# zik-pcb-gpu-f407.net
KiCad netlist of a schematic drawn in EAGLE
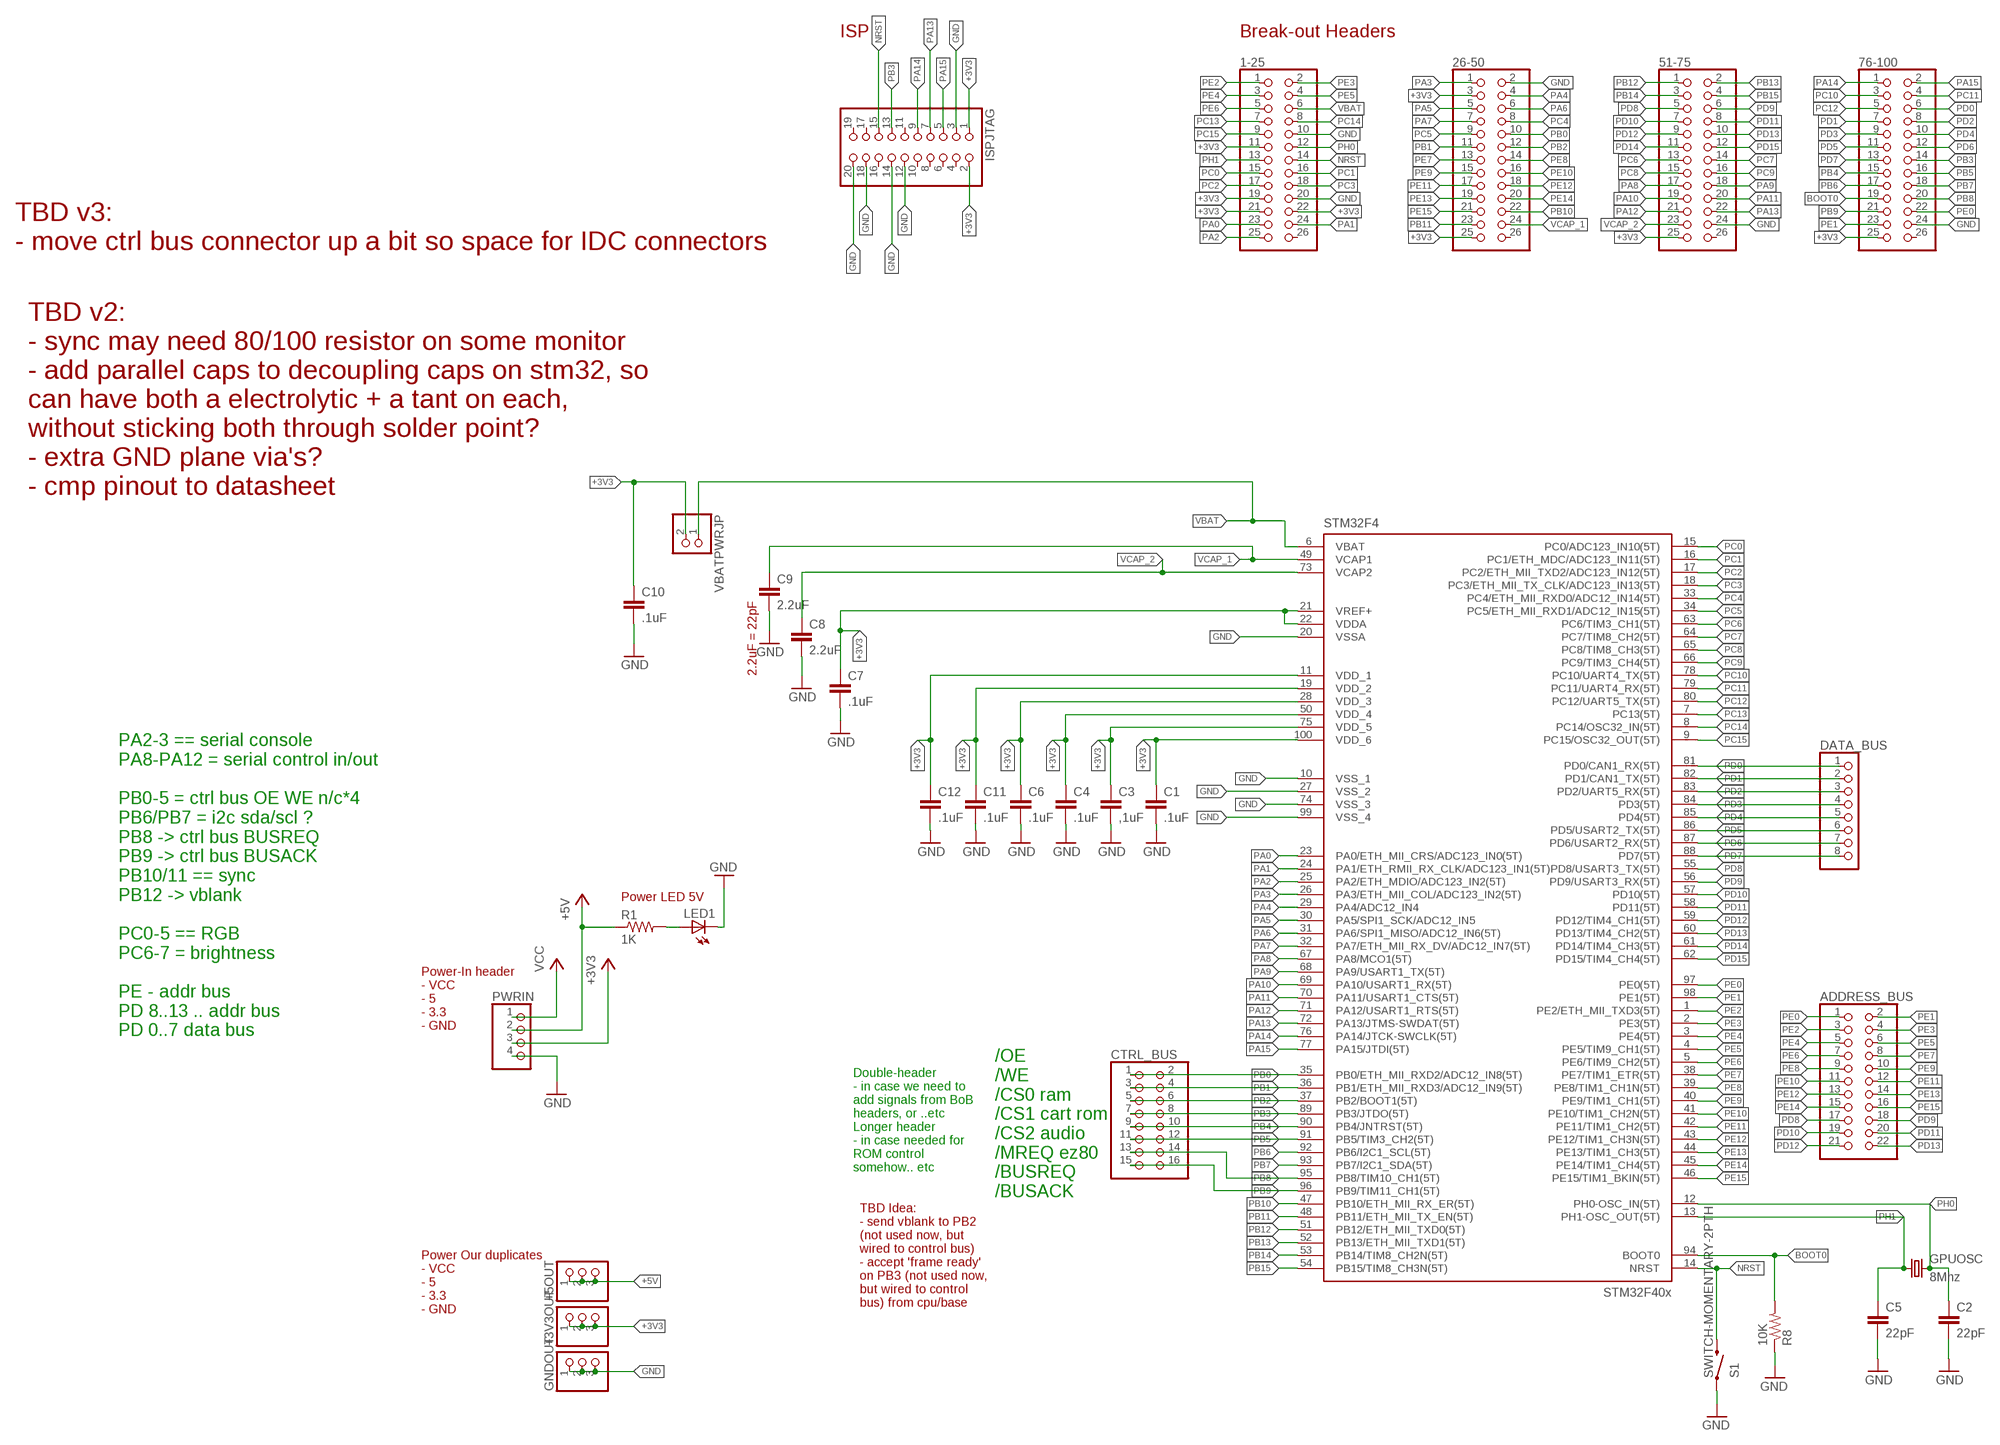
[diagram p0: schematic, sheet 1, part 1 of 2]
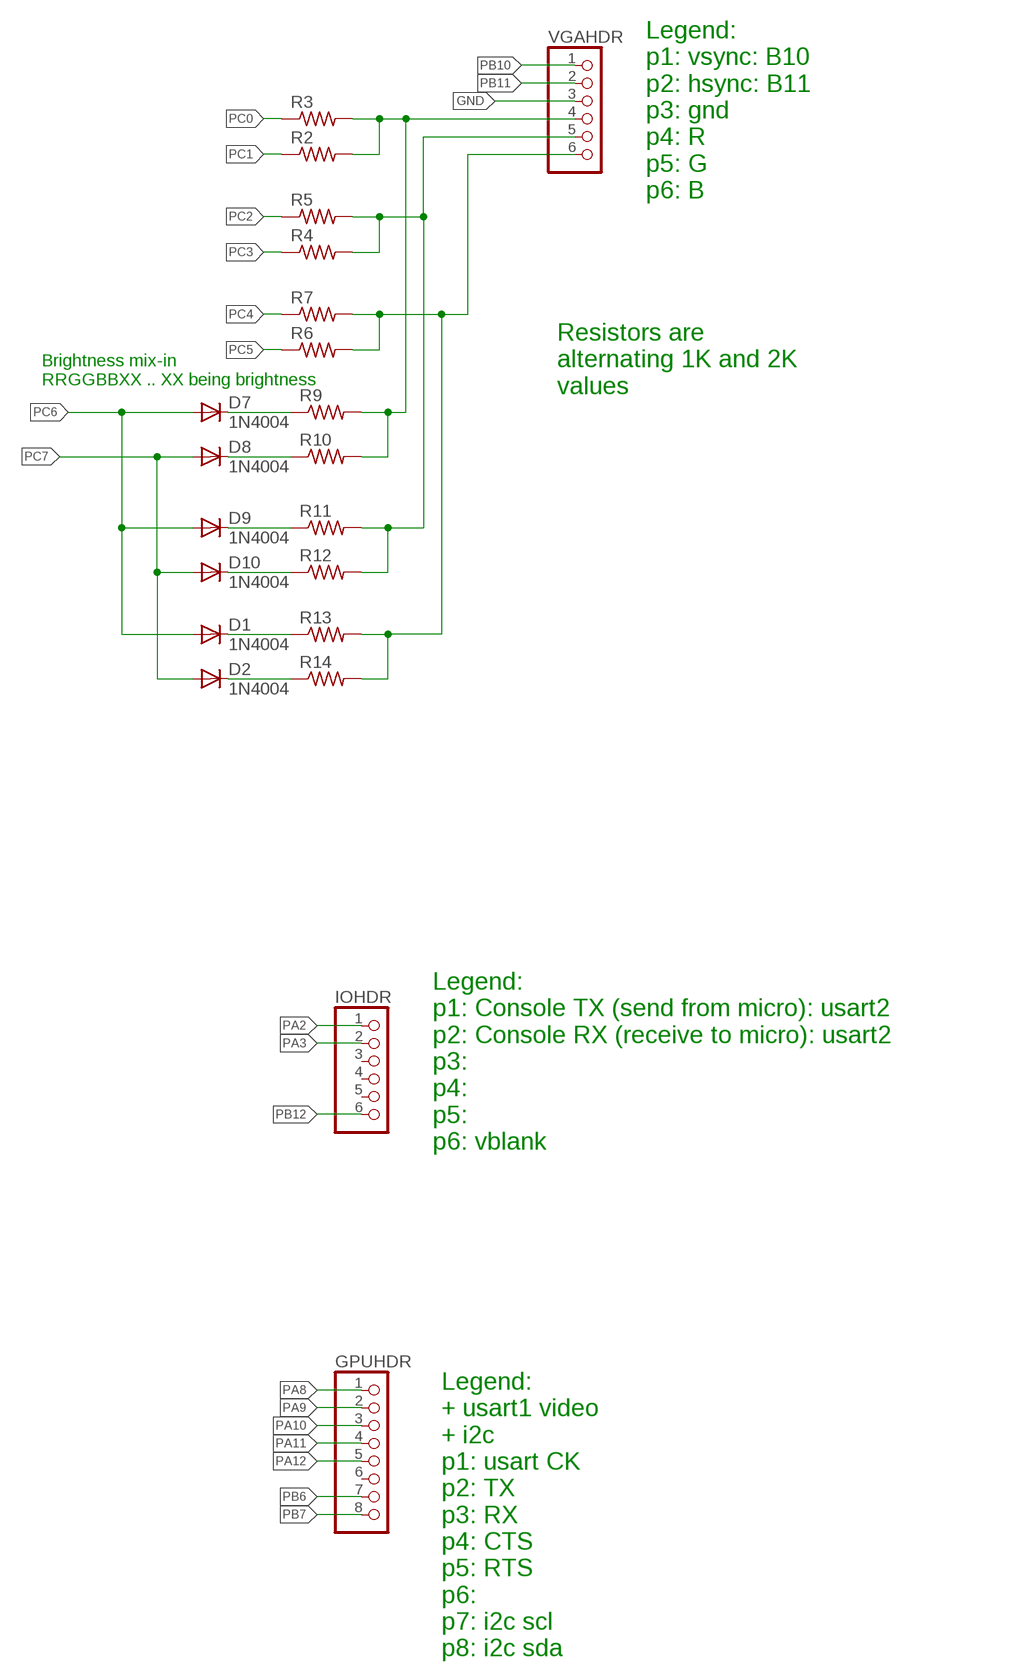
[diagram p1: schematic, sheet 1, part 2 of 2]

(export (version "E")
  (design (tool "Eeschema 10.0.6"))
  (components
    (comp (ref "+3V3OUT")
      (value "PINHD-1X3")
      (footprint "eagle-import:1X03")
      (libsource (lib "eagle-import") (part "PINHD-1X3"))
    )
    (comp (ref "+5OUT")
      (value "PINHD-1X3")
      (footprint "eagle-import:1X03")
      (libsource (lib "eagle-import") (part "PINHD-1X3"))
    )
    (comp (ref "1-25")
      (value "PINHD-2X13")
      (footprint "eagle-import:2X13")
      (libsource (lib "eagle-import") (part "PINHD-2X13"))
    )
    (comp (ref "26-50")
      (value "PINHD-2X13")
      (footprint "eagle-import:2X13")
      (libsource (lib "eagle-import") (part "PINHD-2X13"))
    )
    (comp (ref "51-75")
      (value "PINHD-2X13")
      (footprint "eagle-import:2X13")
      (libsource (lib "eagle-import") (part "PINHD-2X13"))
    )
    (comp (ref "76-100")
      (value "PINHD-2X13")
      (footprint "eagle-import:2X13")
      (libsource (lib "eagle-import") (part "PINHD-2X13"))
    )
    (comp (ref "ADDRESS_BUS")
      (value "PINHD-2X11")
      (footprint "eagle-import:2X11")
      (libsource (lib "eagle-import") (part "PINHD-2X11"))
    )
    (comp (ref "C1")
      (value ".1uF")
      (footprint "eagle-import:C025-025X050")
      (libsource (lib "eagle-import") (part "C-EU025-025X050"))
    )
    (comp (ref "C2")
      (value "22pF")
      (footprint "eagle-import:C025-025X050")
      (libsource (lib "eagle-import") (part "C-EU025-025X050"))
    )
    (comp (ref "C3")
      (value ",1uF")
      (footprint "eagle-import:C025-025X050")
      (libsource (lib "eagle-import") (part "C-EU025-025X050"))
    )
    (comp (ref "C4")
      (value ".1uF")
      (footprint "eagle-import:C025-025X050")
      (libsource (lib "eagle-import") (part "C-EU025-025X050"))
    )
    (comp (ref "C5")
      (value "22pF")
      (footprint "eagle-import:C025-025X050")
      (libsource (lib "eagle-import") (part "C-EU025-025X050"))
    )
    (comp (ref "C6")
      (value ".1uF")
      (footprint "eagle-import:C025-025X050")
      (libsource (lib "eagle-import") (part "C-EU025-025X050"))
    )
    (comp (ref "C7")
      (value ".1uF")
      (footprint "eagle-import:C025-025X050")
      (libsource (lib "eagle-import") (part "C-EU025-025X050"))
    )
    (comp (ref "C8")
      (value "2.2uF")
      (footprint "eagle-import:C025-025X050")
      (libsource (lib "eagle-import") (part "C-EU025-025X050"))
    )
    (comp (ref "C9")
      (value "2.2uF")
      (footprint "eagle-import:C025-025X050")
      (libsource (lib "eagle-import") (part "C-EU025-025X050"))
    )
    (comp (ref "C10")
      (value ".1uF")
      (footprint "eagle-import:C025-025X050")
      (libsource (lib "eagle-import") (part "C-EU025-025X050"))
    )
    (comp (ref "C11")
      (value ".1uF")
      (footprint "eagle-import:C025-025X050")
      (libsource (lib "eagle-import") (part "C-EU025-025X050"))
    )
    (comp (ref "C12")
      (value ".1uF")
      (footprint "eagle-import:C025-025X050")
      (libsource (lib "eagle-import") (part "C-EU025-025X050"))
    )
    (comp (ref "CTRL_BUS")
      (value "PINHD-2X8")
      (footprint "eagle-import:2X08")
      (libsource (lib "eagle-import") (part "PINHD-2X8"))
    )
    (comp (ref "D1")
      (value "1N4004")
      (footprint "eagle-import:DO41-10")
      (libsource (lib "eagle-import") (part "1N4004"))
    )
    (comp (ref "D2")
      (value "1N4004")
      (footprint "eagle-import:DO41-10")
      (libsource (lib "eagle-import") (part "1N4004"))
    )
    (comp (ref "D7")
      (value "1N4004")
      (footprint "eagle-import:DO41-10")
      (libsource (lib "eagle-import") (part "1N4004"))
    )
    (comp (ref "D8")
      (value "1N4004")
      (footprint "eagle-import:DO41-10")
      (libsource (lib "eagle-import") (part "1N4004"))
    )
    (comp (ref "D9")
      (value "1N4004")
      (footprint "eagle-import:DO41-10")
      (libsource (lib "eagle-import") (part "1N4004"))
    )
    (comp (ref "D10")
      (value "1N4004")
      (footprint "eagle-import:DO41-10")
      (libsource (lib "eagle-import") (part "1N4004"))
    )
    (comp (ref "DATA_BUS")
      (value "PINHD-1X8")
      (footprint "eagle-import:1X08")
      (libsource (lib "eagle-import") (part "PINHD-1X8"))
    )
    (comp (ref "GNDOUT")
      (value "PINHD-1X3")
      (footprint "eagle-import:1X03")
      (libsource (lib "eagle-import") (part "PINHD-1X3"))
    )
    (comp (ref "GPUHDR")
      (value "PINHD-1X8")
      (footprint "eagle-import:1X08")
      (libsource (lib "eagle-import") (part "PINHD-1X8"))
    )
    (comp (ref "GPUOSC")
      (value "8Mhz")
      (footprint "eagle-import:HC49US")
      (libsource (lib "eagle-import") (part "CRYSTALHC49US"))
    )
    (comp (ref "IOHDR")
      (value "PINHD-1X6")
      (footprint "eagle-import:1X06")
      (libsource (lib "eagle-import") (part "PINHD-1X6"))
    )
    (comp (ref "ISPJTAG")
      (value "PINHD-2X10")
      (footprint "eagle-import:2X10")
      (libsource (lib "eagle-import") (part "PINHD-2X10"))
    )
    (comp (ref "LED1")
      (value "LED5MM")
      (footprint "eagle-import:LED5MM")
      (libsource (lib "eagle-import") (part "LED5MM"))
    )
    (comp (ref "PWRIN")
      (value "PINHD-1X4")
      (footprint "eagle-import:1X04")
      (libsource (lib "eagle-import") (part "PINHD-1X4"))
    )
    (comp (ref "R1")
      (value "1K")
      (footprint "eagle-import:0207_10")
      (libsource (lib "eagle-import") (part "R-US_0207/10"))
    )
    (comp (ref "R2")
      (value "R-US_0207/10")
      (footprint "eagle-import:0207_10")
      (libsource (lib "eagle-import") (part "R-US_0207/10"))
    )
    (comp (ref "R3")
      (value "R-US_0207/10")
      (footprint "eagle-import:0207_10")
      (libsource (lib "eagle-import") (part "R-US_0207/10"))
    )
    (comp (ref "R4")
      (value "R-US_0207/10")
      (footprint "eagle-import:0207_10")
      (libsource (lib "eagle-import") (part "R-US_0207/10"))
    )
    (comp (ref "R5")
      (value "R-US_0207/10")
      (footprint "eagle-import:0207_10")
      (libsource (lib "eagle-import") (part "R-US_0207/10"))
    )
    (comp (ref "R6")
      (value "R-US_0207/10")
      (footprint "eagle-import:0207_10")
      (libsource (lib "eagle-import") (part "R-US_0207/10"))
    )
    (comp (ref "R7")
      (value "R-US_0207/10")
      (footprint "eagle-import:0207_10")
      (libsource (lib "eagle-import") (part "R-US_0207/10"))
    )
    (comp (ref "R8")
      (value "10K")
      (footprint "eagle-import:0207_10")
      (libsource (lib "eagle-import") (part "R-US_0207/10"))
    )
    (comp (ref "R9")
      (value "R-US_0207/10")
      (footprint "eagle-import:0207_10")
      (libsource (lib "eagle-import") (part "R-US_0207/10"))
    )
    (comp (ref "R10")
      (value "R-US_0207/10")
      (footprint "eagle-import:0207_10")
      (libsource (lib "eagle-import") (part "R-US_0207/10"))
    )
    (comp (ref "R11")
      (value "R-US_0207/10")
      (footprint "eagle-import:0207_10")
      (libsource (lib "eagle-import") (part "R-US_0207/10"))
    )
    (comp (ref "R12")
      (value "R-US_0207/10")
      (footprint "eagle-import:0207_10")
      (libsource (lib "eagle-import") (part "R-US_0207/10"))
    )
    (comp (ref "R13")
      (value "R-US_0207/10")
      (footprint "eagle-import:0207_10")
      (libsource (lib "eagle-import") (part "R-US_0207/10"))
    )
    (comp (ref "R14")
      (value "R-US_0207/10")
      (footprint "eagle-import:0207_10")
      (libsource (lib "eagle-import") (part "R-US_0207/10"))
    )
    (comp (ref "S1")
      (value "SWITCH-MOMENTARY-2PTH")
      (footprint "eagle-import:TACTILE-PTH")
      (libsource (lib "eagle-import") (part "SWITCH-MOMENTARY-2PTH"))
    )
    (comp (ref "STM32F4")
      (value "STM32F407V")
      (footprint "eagle-import:TQFP100")
      (libsource (lib "eagle-import") (part "STM32F407V"))
    )
    (comp (ref "VBATPWRJP")
      (value "PINHD-1X2")
      (footprint "eagle-import:1X02")
      (libsource (lib "eagle-import") (part "PINHD-1X2"))
    )
    (comp (ref "VGAHDR")
      (value "PINHD-1X6")
      (footprint "eagle-import:1X06")
      (libsource (lib "eagle-import") (part "PINHD-1X6"))
    )
  )
  (nets
    (net (code "1") (name "+3V3") (class "Default")
      (node (ref "+3V3OUT") (pin "1") (pinfunction "1_1") (pintype "passive"))
      (node (ref "+3V3OUT") (pin "2") (pinfunction "2_2") (pintype "passive"))
      (node (ref "+3V3OUT") (pin "3") (pinfunction "3_3") (pintype "passive"))
      (node (ref "1-25") (pin "11") (pinfunction "11_11") (pintype "passive"))
      (node (ref "1-25") (pin "19") (pinfunction "19_19") (pintype "passive"))
      (node (ref "1-25") (pin "21") (pinfunction "21_21") (pintype "passive"))
      (node (ref "1-25") (pin "22") (pinfunction "22_22") (pintype "passive"))
      (node (ref "26-50") (pin "25") (pinfunction "25_25") (pintype "passive"))
      (node (ref "26-50") (pin "3") (pinfunction "3_3") (pintype "passive"))
      (node (ref "51-75") (pin "25") (pinfunction "25_25") (pintype "passive"))
      (node (ref "76-100") (pin "25") (pinfunction "25_25") (pintype "passive"))
      (node (ref "C1") (pin "1") (pinfunction "1_1") (pintype "passive"))
      (node (ref "C10") (pin "1") (pinfunction "1_1") (pintype "passive"))
      (node (ref "C11") (pin "1") (pinfunction "1_1") (pintype "passive"))
      (node (ref "C12") (pin "1") (pinfunction "1_1") (pintype "passive"))
      (node (ref "C3") (pin "1") (pinfunction "1_1") (pintype "passive"))
      (node (ref "C4") (pin "1") (pinfunction "1_1") (pintype "passive"))
      (node (ref "C6") (pin "1") (pinfunction "1_1") (pintype "passive"))
      (node (ref "C7") (pin "1") (pinfunction "1_1") (pintype "passive"))
      (node (ref "ISPJTAG") (pin "1") (pinfunction "1_1") (pintype "passive"))
      (node (ref "ISPJTAG") (pin "2") (pinfunction "2_2") (pintype "passive"))
      (node (ref "PWRIN") (pin "3") (pinfunction "3_3") (pintype "passive"))
      (node (ref "STM32F4") (pin "100") (pinfunction "VDD_6_100") (pintype "bidirectional"))
      (node (ref "STM32F4") (pin "11") (pinfunction "VDD_1_11") (pintype "bidirectional"))
      (node (ref "STM32F4") (pin "19") (pinfunction "VDD_2_19") (pintype "bidirectional"))
      (node (ref "STM32F4") (pin "21") (pinfunction "VREF+_21") (pintype "bidirectional"))
      (node (ref "STM32F4") (pin "22") (pinfunction "VDDA_22") (pintype "bidirectional"))
      (node (ref "STM32F4") (pin "28") (pinfunction "VDD_3_28") (pintype "bidirectional"))
      (node (ref "STM32F4") (pin "50") (pinfunction "VDD_4_50") (pintype "bidirectional"))
      (node (ref "STM32F4") (pin "75") (pinfunction "VDD_5_75") (pintype "bidirectional"))
      (node (ref "VBATPWRJP") (pin "2") (pinfunction "2_2") (pintype "passive"))
    )
    (net (code "2") (name "+5V") (class "Default")
      (node (ref "+5OUT") (pin "1") (pinfunction "1_1") (pintype "passive"))
      (node (ref "+5OUT") (pin "2") (pinfunction "2_2") (pintype "passive"))
      (node (ref "+5OUT") (pin "3") (pinfunction "3_3") (pintype "passive"))
      (node (ref "PWRIN") (pin "2") (pinfunction "2_2") (pintype "passive"))
      (node (ref "R1") (pin "1") (pinfunction "1_1") (pintype "passive"))
    )
    (net (code "3") (name "BOOT0") (class "Default")
      (node (ref "76-100") (pin "19") (pinfunction "19_19") (pintype "passive"))
      (node (ref "R8") (pin "2") (pinfunction "2_2") (pintype "passive"))
      (node (ref "STM32F4") (pin "94") (pinfunction "BOOT0_94") (pintype "bidirectional"))
    )
    (net (code "4") (name "GND") (class "Default")
      (node (ref "1-25") (pin "10") (pinfunction "10_10") (pintype "passive"))
      (node (ref "1-25") (pin "20") (pinfunction "20_20") (pintype "passive"))
      (node (ref "26-50") (pin "2") (pinfunction "2_2") (pintype "passive"))
      (node (ref "51-75") (pin "24") (pinfunction "24_24") (pintype "passive"))
      (node (ref "76-100") (pin "24") (pinfunction "24_24") (pintype "passive"))
      (node (ref "C1") (pin "2") (pinfunction "2_2") (pintype "passive"))
      (node (ref "C10") (pin "2") (pinfunction "2_2") (pintype "passive"))
      (node (ref "C11") (pin "2") (pinfunction "2_2") (pintype "passive"))
      (node (ref "C12") (pin "2") (pinfunction "2_2") (pintype "passive"))
      (node (ref "C2") (pin "2") (pinfunction "2_2") (pintype "passive"))
      (node (ref "C3") (pin "2") (pinfunction "2_2") (pintype "passive"))
      (node (ref "C4") (pin "2") (pinfunction "2_2") (pintype "passive"))
      (node (ref "C5") (pin "2") (pinfunction "2_2") (pintype "passive"))
      (node (ref "C6") (pin "2") (pinfunction "2_2") (pintype "passive"))
      (node (ref "C7") (pin "2") (pinfunction "2_2") (pintype "passive"))
      (node (ref "C8") (pin "2") (pinfunction "2_2") (pintype "passive"))
      (node (ref "C9") (pin "2") (pinfunction "2_2") (pintype "passive"))
      (node (ref "GNDOUT") (pin "1") (pinfunction "1_1") (pintype "passive"))
      (node (ref "GNDOUT") (pin "2") (pinfunction "2_2") (pintype "passive"))
      (node (ref "GNDOUT") (pin "3") (pinfunction "3_3") (pintype "passive"))
      (node (ref "ISPJTAG") (pin "12") (pinfunction "12_12") (pintype "passive"))
      (node (ref "ISPJTAG") (pin "14") (pinfunction "14_14") (pintype "passive"))
      (node (ref "ISPJTAG") (pin "18") (pinfunction "18_18") (pintype "passive"))
      (node (ref "ISPJTAG") (pin "20") (pinfunction "20_20") (pintype "passive"))
      (node (ref "ISPJTAG") (pin "3") (pinfunction "3_3") (pintype "passive"))
      (node (ref "LED1") (pin "K") (pinfunction "C_K") (pintype "passive"))
      (node (ref "PWRIN") (pin "4") (pinfunction "4_4") (pintype "passive"))
      (node (ref "R8") (pin "1") (pinfunction "1_1") (pintype "passive"))
      (node (ref "S1") (pin "1") (pinfunction "1_1") (pintype "passive"))
      (node (ref "STM32F4") (pin "10") (pinfunction "VSS_1_10") (pintype "bidirectional"))
      (node (ref "STM32F4") (pin "20") (pinfunction "VSSA_20") (pintype "bidirectional"))
      (node (ref "STM32F4") (pin "27") (pinfunction "VSS_2_27") (pintype "bidirectional"))
      (node (ref "STM32F4") (pin "74") (pinfunction "VSS_3_74") (pintype "bidirectional"))
      (node (ref "STM32F4") (pin "99") (pinfunction "VSS_4_99") (pintype "bidirectional"))
      (node (ref "VGAHDR") (pin "3") (pinfunction "3_3") (pintype "passive"))
    )
    (net (code "5") (name "NRST") (class "Default")
      (node (ref "1-25") (pin "14") (pinfunction "14_14") (pintype "passive"))
      (node (ref "ISPJTAG") (pin "15") (pinfunction "15_15") (pintype "passive"))
      (node (ref "S1") (pin "3") (pinfunction "2_3") (pintype "passive"))
      (node (ref "STM32F4") (pin "14") (pinfunction "NRST_14") (pintype "bidirectional"))
    )
    (net (code "6") (name "Net-(D1-PadC)") (class "Default")
      (node (ref "D1") (pin "C") (pinfunction "C_C") (pintype "passive"))
      (node (ref "R13") (pin "1") (pinfunction "1_1") (pintype "passive"))
    )
    (net (code "7") (name "Net-(D2-PadC)") (class "Default")
      (node (ref "D2") (pin "C") (pinfunction "C_C") (pintype "passive"))
      (node (ref "R14") (pin "1") (pinfunction "1_1") (pintype "passive"))
    )
    (net (code "8") (name "Net-(D7-PadC)") (class "Default")
      (node (ref "D7") (pin "C") (pinfunction "C_C") (pintype "passive"))
      (node (ref "R9") (pin "1") (pinfunction "1_1") (pintype "passive"))
    )
    (net (code "9") (name "Net-(D8-PadC)") (class "Default")
      (node (ref "D8") (pin "C") (pinfunction "C_C") (pintype "passive"))
      (node (ref "R10") (pin "1") (pinfunction "1_1") (pintype "passive"))
    )
    (net (code "10") (name "Net-(D9-PadC)") (class "Default")
      (node (ref "D9") (pin "C") (pinfunction "C_C") (pintype "passive"))
      (node (ref "R11") (pin "1") (pinfunction "1_1") (pintype "passive"))
    )
    (net (code "11") (name "Net-(D10-PadC)") (class "Default")
      (node (ref "D10") (pin "C") (pinfunction "C_C") (pintype "passive"))
      (node (ref "R12") (pin "1") (pinfunction "1_1") (pintype "passive"))
    )
    (net (code "12") (name "Net-(LED1-PadA)") (class "Default")
      (node (ref "LED1") (pin "A") (pinfunction "A_A") (pintype "passive"))
      (node (ref "R1") (pin "2") (pinfunction "2_2") (pintype "passive"))
    )
    (net (code "13") (name "Net-(R10-Pad2)") (class "Default")
      (node (ref "R10") (pin "2") (pinfunction "2_2") (pintype "passive"))
      (node (ref "R2") (pin "2") (pinfunction "2_2") (pintype "passive"))
      (node (ref "R3") (pin "2") (pinfunction "2_2") (pintype "passive"))
      (node (ref "R9") (pin "2") (pinfunction "2_2") (pintype "passive"))
      (node (ref "VGAHDR") (pin "4") (pinfunction "4_4") (pintype "passive"))
    )
    (net (code "14") (name "Net-(R11-Pad2)") (class "Default")
      (node (ref "R11") (pin "2") (pinfunction "2_2") (pintype "passive"))
      (node (ref "R12") (pin "2") (pinfunction "2_2") (pintype "passive"))
      (node (ref "R4") (pin "2") (pinfunction "2_2") (pintype "passive"))
      (node (ref "R5") (pin "2") (pinfunction "2_2") (pintype "passive"))
      (node (ref "VGAHDR") (pin "5") (pinfunction "5_5") (pintype "passive"))
    )
    (net (code "15") (name "Net-(R13-Pad2)") (class "Default")
      (node (ref "R13") (pin "2") (pinfunction "2_2") (pintype "passive"))
      (node (ref "R14") (pin "2") (pinfunction "2_2") (pintype "passive"))
      (node (ref "R6") (pin "2") (pinfunction "2_2") (pintype "passive"))
      (node (ref "R7") (pin "2") (pinfunction "2_2") (pintype "passive"))
      (node (ref "VGAHDR") (pin "6") (pinfunction "6_6") (pintype "passive"))
    )
    (net (code "16") (name "PA0") (class "Default")
      (node (ref "1-25") (pin "23") (pinfunction "23_23") (pintype "passive"))
      (node (ref "STM32F4") (pin "23") (pinfunction "PA0/ETH_MII_CRS/ADC123_IN0(5T)_23") (pintype "bidirectional"))
    )
    (net (code "17") (name "PA1") (class "Default")
      (node (ref "1-25") (pin "24") (pinfunction "24_24") (pintype "passive"))
      (node (ref "STM32F4") (pin "24") (pinfunction "PA1/ETH_RMII_RX_CLK/ADC123_IN1(5T)_24") (pintype "bidirectional"))
    )
    (net (code "18") (name "PA2") (class "Default")
      (node (ref "1-25") (pin "25") (pinfunction "25_25") (pintype "passive"))
      (node (ref "IOHDR") (pin "1") (pinfunction "1_1") (pintype "passive"))
      (node (ref "STM32F4") (pin "25") (pinfunction "PA2/ETH_MDIO/ADC123_IN2(5T)_25") (pintype "bidirectional"))
    )
    (net (code "19") (name "PA3") (class "Default")
      (node (ref "26-50") (pin "1") (pinfunction "1_1") (pintype "passive"))
      (node (ref "IOHDR") (pin "2") (pinfunction "2_2") (pintype "passive"))
      (node (ref "STM32F4") (pin "26") (pinfunction "PA3/ETH_MII_COL/ADC123_IN2(5T)_26") (pintype "bidirectional"))
    )
    (net (code "20") (name "PA4") (class "Default")
      (node (ref "26-50") (pin "4") (pinfunction "4_4") (pintype "passive"))
      (node (ref "STM32F4") (pin "29") (pinfunction "PA4/ADC12_IN4_29") (pintype "bidirectional"))
    )
    (net (code "21") (name "PA5") (class "Default")
      (node (ref "26-50") (pin "5") (pinfunction "5_5") (pintype "passive"))
      (node (ref "STM32F4") (pin "30") (pinfunction "PA5/SPI1_SCK/ADC12_IN5_30") (pintype "bidirectional"))
    )
    (net (code "22") (name "PA6") (class "Default")
      (node (ref "26-50") (pin "6") (pinfunction "6_6") (pintype "passive"))
      (node (ref "STM32F4") (pin "31") (pinfunction "PA6/SPI1_MISO/ADC12_IN6(5T)_31") (pintype "bidirectional"))
    )
    (net (code "23") (name "PA7") (class "Default")
      (node (ref "26-50") (pin "7") (pinfunction "7_7") (pintype "passive"))
      (node (ref "STM32F4") (pin "32") (pinfunction "PA7/ETH_MII_RX_DV/ADC12_IN7(5T)_32") (pintype "bidirectional"))
    )
    (net (code "24") (name "PA8") (class "Default")
      (node (ref "51-75") (pin "17") (pinfunction "17_17") (pintype "passive"))
      (node (ref "GPUHDR") (pin "1") (pinfunction "1_1") (pintype "passive"))
      (node (ref "STM32F4") (pin "67") (pinfunction "PA8/MCO1(5T)_67") (pintype "bidirectional"))
    )
    (net (code "25") (name "PA9") (class "Default")
      (node (ref "51-75") (pin "18") (pinfunction "18_18") (pintype "passive"))
      (node (ref "GPUHDR") (pin "2") (pinfunction "2_2") (pintype "passive"))
      (node (ref "STM32F4") (pin "68") (pinfunction "PA9/USART1_TX(5T)_68") (pintype "bidirectional"))
    )
    (net (code "26") (name "PA10") (class "Default")
      (node (ref "51-75") (pin "19") (pinfunction "19_19") (pintype "passive"))
      (node (ref "GPUHDR") (pin "3") (pinfunction "3_3") (pintype "passive"))
      (node (ref "STM32F4") (pin "69") (pinfunction "PA10/USART1_RX(5T)_69") (pintype "bidirectional"))
    )
    (net (code "27") (name "PA11") (class "Default")
      (node (ref "51-75") (pin "20") (pinfunction "20_20") (pintype "passive"))
      (node (ref "GPUHDR") (pin "4") (pinfunction "4_4") (pintype "passive"))
      (node (ref "STM32F4") (pin "70") (pinfunction "PA11/USART1_CTS(5T)_70") (pintype "bidirectional"))
    )
    (net (code "28") (name "PA12") (class "Default")
      (node (ref "51-75") (pin "21") (pinfunction "21_21") (pintype "passive"))
      (node (ref "GPUHDR") (pin "5") (pinfunction "5_5") (pintype "passive"))
      (node (ref "STM32F4") (pin "71") (pinfunction "PA12/USART1_RTS(5T)_71") (pintype "bidirectional"))
    )
    (net (code "29") (name "PA13") (class "Default")
      (node (ref "51-75") (pin "22") (pinfunction "22_22") (pintype "passive"))
      (node (ref "ISPJTAG") (pin "7") (pinfunction "7_7") (pintype "passive"))
      (node (ref "STM32F4") (pin "72") (pinfunction "PA13/JTMS-SWDAT(5T)_72") (pintype "bidirectional"))
    )
    (net (code "30") (name "PA14") (class "Default")
      (node (ref "76-100") (pin "1") (pinfunction "1_1") (pintype "passive"))
      (node (ref "ISPJTAG") (pin "9") (pinfunction "9_9") (pintype "passive"))
      (node (ref "STM32F4") (pin "76") (pinfunction "PA14/JTCK-SWCLK(5T)_76") (pintype "bidirectional"))
    )
    (net (code "31") (name "PA15") (class "Default")
      (node (ref "76-100") (pin "2") (pinfunction "2_2") (pintype "passive"))
      (node (ref "ISPJTAG") (pin "5") (pinfunction "5_5") (pintype "passive"))
      (node (ref "STM32F4") (pin "77") (pinfunction "PA15/JTDI(5T)_77") (pintype "bidirectional"))
    )
    (net (code "32") (name "PB0") (class "Default")
      (node (ref "26-50") (pin "10") (pinfunction "10_10") (pintype "passive"))
      (node (ref "CTRL_BUS") (pin "1") (pinfunction "1_1") (pintype "passive"))
      (node (ref "CTRL_BUS") (pin "2") (pinfunction "2_2") (pintype "passive"))
      (node (ref "STM32F4") (pin "35") (pinfunction "PB0/ETH_MII_RXD2/ADC12_IN8(5T)_35") (pintype "bidirectional"))
    )
    (net (code "33") (name "PB1") (class "Default")
      (node (ref "26-50") (pin "11") (pinfunction "11_11") (pintype "passive"))
      (node (ref "CTRL_BUS") (pin "3") (pinfunction "3_3") (pintype "passive"))
      (node (ref "CTRL_BUS") (pin "4") (pinfunction "4_4") (pintype "passive"))
      (node (ref "STM32F4") (pin "36") (pinfunction "PB1/ETH_MII_RXD3/ADC12_IN9(5T)_36") (pintype "bidirectional"))
    )
    (net (code "34") (name "PB2") (class "Default")
      (node (ref "26-50") (pin "12") (pinfunction "12_12") (pintype "passive"))
      (node (ref "CTRL_BUS") (pin "5") (pinfunction "5_5") (pintype "passive"))
      (node (ref "CTRL_BUS") (pin "6") (pinfunction "6_6") (pintype "passive"))
      (node (ref "STM32F4") (pin "37") (pinfunction "PB2/BOOT1(5T)_37") (pintype "bidirectional"))
    )
    (net (code "35") (name "PB3") (class "Default")
      (node (ref "76-100") (pin "14") (pinfunction "14_14") (pintype "passive"))
      (node (ref "CTRL_BUS") (pin "7") (pinfunction "7_7") (pintype "passive"))
      (node (ref "CTRL_BUS") (pin "8") (pinfunction "8_8") (pintype "passive"))
      (node (ref "ISPJTAG") (pin "13") (pinfunction "13_13") (pintype "passive"))
      (node (ref "STM32F4") (pin "89") (pinfunction "PB3/JTDO(5T)_89") (pintype "bidirectional"))
    )
    (net (code "36") (name "PB4") (class "Default")
      (node (ref "76-100") (pin "15") (pinfunction "15_15") (pintype "passive"))
      (node (ref "CTRL_BUS") (pin "10") (pinfunction "10_10") (pintype "passive"))
      (node (ref "CTRL_BUS") (pin "9") (pinfunction "9_9") (pintype "passive"))
      (node (ref "STM32F4") (pin "90") (pinfunction "PB4/JNTRST(5T)_90") (pintype "bidirectional"))
    )
    (net (code "37") (name "PB5") (class "Default")
      (node (ref "76-100") (pin "16") (pinfunction "16_16") (pintype "passive"))
      (node (ref "CTRL_BUS") (pin "11") (pinfunction "11_11") (pintype "passive"))
      (node (ref "CTRL_BUS") (pin "12") (pinfunction "12_12") (pintype "passive"))
      (node (ref "STM32F4") (pin "91") (pinfunction "PB5/TIM3_CH2(5T)_91") (pintype "bidirectional"))
    )
    (net (code "38") (name "PB6") (class "Default")
      (node (ref "76-100") (pin "17") (pinfunction "17_17") (pintype "passive"))
      (node (ref "GPUHDR") (pin "7") (pinfunction "7_7") (pintype "passive"))
      (node (ref "STM32F4") (pin "92") (pinfunction "PB6/I2C1_SCL(5T)_92") (pintype "bidirectional"))
    )
    (net (code "39") (name "PB7") (class "Default")
      (node (ref "76-100") (pin "18") (pinfunction "18_18") (pintype "passive"))
      (node (ref "GPUHDR") (pin "8") (pinfunction "8_8") (pintype "passive"))
      (node (ref "STM32F4") (pin "93") (pinfunction "PB7/I2C1_SDA(5T)_93") (pintype "bidirectional"))
    )
    (net (code "40") (name "PB8") (class "Default")
      (node (ref "76-100") (pin "20") (pinfunction "20_20") (pintype "passive"))
      (node (ref "CTRL_BUS") (pin "13") (pinfunction "13_13") (pintype "passive"))
      (node (ref "CTRL_BUS") (pin "14") (pinfunction "14_14") (pintype "passive"))
      (node (ref "STM32F4") (pin "95") (pinfunction "PB8/TIM10_CH1(5T)_95") (pintype "bidirectional"))
    )
    (net (code "41") (name "PB9") (class "Default")
      (node (ref "76-100") (pin "21") (pinfunction "21_21") (pintype "passive"))
      (node (ref "CTRL_BUS") (pin "15") (pinfunction "15_15") (pintype "passive"))
      (node (ref "CTRL_BUS") (pin "16") (pinfunction "16_16") (pintype "passive"))
      (node (ref "STM32F4") (pin "96") (pinfunction "PB9/TIM11_CH1(5T)_96") (pintype "bidirectional"))
    )
    (net (code "42") (name "PB10") (class "Default")
      (node (ref "26-50") (pin "22") (pinfunction "22_22") (pintype "passive"))
      (node (ref "STM32F4") (pin "47") (pinfunction "PB10/ETH_MII_RX_ER(5T)_47") (pintype "bidirectional"))
      (node (ref "VGAHDR") (pin "1") (pinfunction "1_1") (pintype "passive"))
    )
    (net (code "43") (name "PB11") (class "Default")
      (node (ref "26-50") (pin "23") (pinfunction "23_23") (pintype "passive"))
      (node (ref "STM32F4") (pin "48") (pinfunction "PB11/ETH_MII_TX_EN(5T)_48") (pintype "bidirectional"))
      (node (ref "VGAHDR") (pin "2") (pinfunction "2_2") (pintype "passive"))
    )
    (net (code "44") (name "PB12") (class "Default")
      (node (ref "51-75") (pin "1") (pinfunction "1_1") (pintype "passive"))
      (node (ref "IOHDR") (pin "6") (pinfunction "6_6") (pintype "passive"))
      (node (ref "STM32F4") (pin "51") (pinfunction "PB12/ETH_MII_TXD0(5T)_51") (pintype "bidirectional"))
    )
    (net (code "45") (name "PB13") (class "Default")
      (node (ref "51-75") (pin "2") (pinfunction "2_2") (pintype "passive"))
      (node (ref "STM32F4") (pin "52") (pinfunction "PB13/ETH_MII_TXD1(5T)_52") (pintype "bidirectional"))
    )
    (net (code "46") (name "PB14") (class "Default")
      (node (ref "51-75") (pin "3") (pinfunction "3_3") (pintype "passive"))
      (node (ref "STM32F4") (pin "53") (pinfunction "PB14/TIM8_CH2N(5T)_53") (pintype "bidirectional"))
    )
    (net (code "47") (name "PB15") (class "Default")
      (node (ref "51-75") (pin "4") (pinfunction "4_4") (pintype "passive"))
      (node (ref "STM32F4") (pin "54") (pinfunction "PB15/TIM8_CH3N(5T)_54") (pintype "bidirectional"))
    )
    (net (code "48") (name "PC0") (class "Default")
      (node (ref "1-25") (pin "15") (pinfunction "15_15") (pintype "passive"))
      (node (ref "R3") (pin "1") (pinfunction "1_1") (pintype "passive"))
      (node (ref "STM32F4") (pin "15") (pinfunction "PC0/ADC123_IN10(5T)_15") (pintype "bidirectional"))
    )
    (net (code "49") (name "PC1") (class "Default")
      (node (ref "1-25") (pin "16") (pinfunction "16_16") (pintype "passive"))
      (node (ref "R2") (pin "1") (pinfunction "1_1") (pintype "passive"))
      (node (ref "STM32F4") (pin "16") (pinfunction "PC1/ETH_MDC/ADC123_IN11(5T)_16") (pintype "bidirectional"))
    )
    (net (code "50") (name "PC2") (class "Default")
      (node (ref "1-25") (pin "17") (pinfunction "17_17") (pintype "passive"))
      (node (ref "R5") (pin "1") (pinfunction "1_1") (pintype "passive"))
      (node (ref "STM32F4") (pin "17") (pinfunction "PC2/ETH_MII_TXD2/ADC123_IN12(5T)_17") (pintype "bidirectional"))
    )
    (net (code "51") (name "PC3") (class "Default")
      (node (ref "1-25") (pin "18") (pinfunction "18_18") (pintype "passive"))
      (node (ref "R4") (pin "1") (pinfunction "1_1") (pintype "passive"))
      (node (ref "STM32F4") (pin "18") (pinfunction "PC3/ETH_MII_TX_CLK/ADC123_IN13(5T)_18") (pintype "bidirectional"))
    )
    (net (code "52") (name "PC4") (class "Default")
      (node (ref "26-50") (pin "8") (pinfunction "8_8") (pintype "passive"))
      (node (ref "R7") (pin "1") (pinfunction "1_1") (pintype "passive"))
      (node (ref "STM32F4") (pin "33") (pinfunction "PC4/ETH_MII_RXD0/ADC12_IN14(5T)_33") (pintype "bidirectional"))
    )
    (net (code "53") (name "PC5") (class "Default")
      (node (ref "26-50") (pin "9") (pinfunction "9_9") (pintype "passive"))
      (node (ref "R6") (pin "1") (pinfunction "1_1") (pintype "passive"))
      (node (ref "STM32F4") (pin "34") (pinfunction "PC5/ETH_MII_RXD1/ADC12_IN15(5T)_34") (pintype "bidirectional"))
    )
    (net (code "54") (name "PC6") (class "Default")
      (node (ref "51-75") (pin "13") (pinfunction "13_13") (pintype "passive"))
      (node (ref "D1") (pin "A") (pinfunction "A_A") (pintype "passive"))
      (node (ref "D7") (pin "A") (pinfunction "A_A") (pintype "passive"))
      (node (ref "D9") (pin "A") (pinfunction "A_A") (pintype "passive"))
      (node (ref "STM32F4") (pin "63") (pinfunction "PC6/TIM3_CH1(5T)_63") (pintype "bidirectional"))
    )
    (net (code "55") (name "PC7") (class "Default")
      (node (ref "51-75") (pin "14") (pinfunction "14_14") (pintype "passive"))
      (node (ref "D10") (pin "A") (pinfunction "A_A") (pintype "passive"))
      (node (ref "D2") (pin "A") (pinfunction "A_A") (pintype "passive"))
      (node (ref "D8") (pin "A") (pinfunction "A_A") (pintype "passive"))
      (node (ref "STM32F4") (pin "64") (pinfunction "PC7/TIM8_CH2(5T)_64") (pintype "bidirectional"))
    )
    (net (code "56") (name "PC8") (class "Default")
      (node (ref "51-75") (pin "15") (pinfunction "15_15") (pintype "passive"))
      (node (ref "STM32F4") (pin "65") (pinfunction "PC8/TIM8_CH3(5T)_65") (pintype "bidirectional"))
    )
    (net (code "57") (name "PC9") (class "Default")
      (node (ref "51-75") (pin "16") (pinfunction "16_16") (pintype "passive"))
      (node (ref "STM32F4") (pin "66") (pinfunction "PC9/TIM3_CH4(5T)_66") (pintype "bidirectional"))
    )
    (net (code "58") (name "PC10") (class "Default")
      (node (ref "76-100") (pin "3") (pinfunction "3_3") (pintype "passive"))
      (node (ref "STM32F4") (pin "78") (pinfunction "PC10/UART4_TX(5T)_78") (pintype "bidirectional"))
    )
    (net (code "59") (name "PC11") (class "Default")
      (node (ref "76-100") (pin "4") (pinfunction "4_4") (pintype "passive"))
      (node (ref "STM32F4") (pin "79") (pinfunction "PC11/UART4_RX(5T)_79") (pintype "bidirectional"))
    )
    (net (code "60") (name "PC12") (class "Default")
      (node (ref "76-100") (pin "5") (pinfunction "5_5") (pintype "passive"))
      (node (ref "STM32F4") (pin "80") (pinfunction "PC12/UART5_TX(5T)_80") (pintype "bidirectional"))
    )
    (net (code "61") (name "PC13") (class "Default")
      (node (ref "1-25") (pin "7") (pinfunction "7_7") (pintype "passive"))
      (node (ref "STM32F4") (pin "7") (pinfunction "PC13(5T)_7") (pintype "bidirectional"))
    )
    (net (code "62") (name "PC14") (class "Default")
      (node (ref "1-25") (pin "8") (pinfunction "8_8") (pintype "passive"))
      (node (ref "STM32F4") (pin "8") (pinfunction "PC14/OSC32_IN(5T)_8") (pintype "bidirectional"))
    )
    (net (code "63") (name "PC15") (class "Default")
      (node (ref "1-25") (pin "9") (pinfunction "9_9") (pintype "passive"))
      (node (ref "STM32F4") (pin "9") (pinfunction "PC15/OSC32_OUT(5T)_9") (pintype "bidirectional"))
    )
    (net (code "64") (name "PD0") (class "Default")
      (node (ref "76-100") (pin "6") (pinfunction "6_6") (pintype "passive"))
      (node (ref "DATA_BUS") (pin "1") (pinfunction "1_1") (pintype "passive"))
      (node (ref "STM32F4") (pin "81") (pinfunction "PD0/CAN1_RX(5T)_81") (pintype "bidirectional"))
    )
    (net (code "65") (name "PD1") (class "Default")
      (node (ref "76-100") (pin "7") (pinfunction "7_7") (pintype "passive"))
      (node (ref "DATA_BUS") (pin "2") (pinfunction "2_2") (pintype "passive"))
      (node (ref "STM32F4") (pin "82") (pinfunction "PD1/CAN1_TX(5T)_82") (pintype "bidirectional"))
    )
    (net (code "66") (name "PD2") (class "Default")
      (node (ref "76-100") (pin "8") (pinfunction "8_8") (pintype "passive"))
      (node (ref "DATA_BUS") (pin "3") (pinfunction "3_3") (pintype "passive"))
      (node (ref "STM32F4") (pin "83") (pinfunction "PD2/UART5_RX(5T)_83") (pintype "bidirectional"))
    )
    (net (code "67") (name "PD3") (class "Default")
      (node (ref "76-100") (pin "9") (pinfunction "9_9") (pintype "passive"))
      (node (ref "DATA_BUS") (pin "4") (pinfunction "4_4") (pintype "passive"))
      (node (ref "STM32F4") (pin "84") (pinfunction "PD3(5T)_84") (pintype "bidirectional"))
    )
    (net (code "68") (name "PD4") (class "Default")
      (node (ref "76-100") (pin "10") (pinfunction "10_10") (pintype "passive"))
      (node (ref "DATA_BUS") (pin "5") (pinfunction "5_5") (pintype "passive"))
      (node (ref "STM32F4") (pin "85") (pinfunction "PD4(5T)_85") (pintype "bidirectional"))
    )
    (net (code "69") (name "PD5") (class "Default")
      (node (ref "76-100") (pin "11") (pinfunction "11_11") (pintype "passive"))
      (node (ref "DATA_BUS") (pin "6") (pinfunction "6_6") (pintype "passive"))
      (node (ref "STM32F4") (pin "86") (pinfunction "PD5/USART2_TX(5T)_86") (pintype "bidirectional"))
    )
    (net (code "70") (name "PD6") (class "Default")
      (node (ref "76-100") (pin "12") (pinfunction "12_12") (pintype "passive"))
      (node (ref "DATA_BUS") (pin "7") (pinfunction "7_7") (pintype "passive"))
      (node (ref "STM32F4") (pin "87") (pinfunction "PD6/USART2_RX(5T)_87") (pintype "bidirectional"))
    )
    (net (code "71") (name "PD7") (class "Default")
      (node (ref "76-100") (pin "13") (pinfunction "13_13") (pintype "passive"))
      (node (ref "DATA_BUS") (pin "8") (pinfunction "8_8") (pintype "passive"))
      (node (ref "STM32F4") (pin "88") (pinfunction "PD7(5T)_88") (pintype "bidirectional"))
    )
    (net (code "72") (name "PD8") (class "Default")
      (node (ref "51-75") (pin "5") (pinfunction "5_5") (pintype "passive"))
      (node (ref "ADDRESS_BUS") (pin "17") (pinfunction "17_17") (pintype "passive"))
      (node (ref "STM32F4") (pin "55") (pinfunction "PD8/USART3_TX(5T)_55") (pintype "bidirectional"))
    )
    (net (code "73") (name "PD9") (class "Default")
      (node (ref "51-75") (pin "6") (pinfunction "6_6") (pintype "passive"))
      (node (ref "ADDRESS_BUS") (pin "18") (pinfunction "18_18") (pintype "passive"))
      (node (ref "STM32F4") (pin "56") (pinfunction "PD9/USART3_RX(5T)_56") (pintype "bidirectional"))
    )
    (net (code "74") (name "PD10") (class "Default")
      (node (ref "51-75") (pin "7") (pinfunction "7_7") (pintype "passive"))
      (node (ref "ADDRESS_BUS") (pin "19") (pinfunction "19_19") (pintype "passive"))
      (node (ref "STM32F4") (pin "57") (pinfunction "PD10(5T)_57") (pintype "bidirectional"))
    )
    (net (code "75") (name "PD11") (class "Default")
      (node (ref "51-75") (pin "8") (pinfunction "8_8") (pintype "passive"))
      (node (ref "ADDRESS_BUS") (pin "20") (pinfunction "20_20") (pintype "passive"))
      (node (ref "STM32F4") (pin "58") (pinfunction "PD11(5T)_58") (pintype "bidirectional"))
    )
    (net (code "76") (name "PD12") (class "Default")
      (node (ref "51-75") (pin "9") (pinfunction "9_9") (pintype "passive"))
      (node (ref "ADDRESS_BUS") (pin "21") (pinfunction "21_21") (pintype "passive"))
      (node (ref "STM32F4") (pin "59") (pinfunction "PD12/TIM4_CH1(5T)_59") (pintype "bidirectional"))
    )
    (net (code "77") (name "PD13") (class "Default")
      (node (ref "51-75") (pin "10") (pinfunction "10_10") (pintype "passive"))
      (node (ref "ADDRESS_BUS") (pin "22") (pinfunction "22_22") (pintype "passive"))
      (node (ref "STM32F4") (pin "60") (pinfunction "PD13/TIM4_CH2(5T)_60") (pintype "bidirectional"))
    )
    (net (code "78") (name "PD14") (class "Default")
      (node (ref "51-75") (pin "11") (pinfunction "11_11") (pintype "passive"))
      (node (ref "STM32F4") (pin "61") (pinfunction "PD14/TIM4_CH3(5T)_61") (pintype "bidirectional"))
    )
    (net (code "79") (name "PD15") (class "Default")
      (node (ref "51-75") (pin "12") (pinfunction "12_12") (pintype "passive"))
      (node (ref "STM32F4") (pin "62") (pinfunction "PD15/TIM4_CH4(5T)_62") (pintype "bidirectional"))
    )
    (net (code "80") (name "PE0") (class "Default")
      (node (ref "76-100") (pin "22") (pinfunction "22_22") (pintype "passive"))
      (node (ref "ADDRESS_BUS") (pin "1") (pinfunction "1_1") (pintype "passive"))
      (node (ref "STM32F4") (pin "97") (pinfunction "PE0(5T)_97") (pintype "bidirectional"))
    )
    (net (code "81") (name "PE1") (class "Default")
      (node (ref "76-100") (pin "23") (pinfunction "23_23") (pintype "passive"))
      (node (ref "ADDRESS_BUS") (pin "2") (pinfunction "2_2") (pintype "passive"))
      (node (ref "STM32F4") (pin "98") (pinfunction "PE1(5T)_98") (pintype "bidirectional"))
    )
    (net (code "82") (name "PE2") (class "Default")
      (node (ref "1-25") (pin "1") (pinfunction "1_1") (pintype "passive"))
      (node (ref "ADDRESS_BUS") (pin "3") (pinfunction "3_3") (pintype "passive"))
      (node (ref "STM32F4") (pin "1") (pinfunction "PE2/ETH_MII_TXD3(5T)_1") (pintype "bidirectional"))
    )
    (net (code "83") (name "PE3") (class "Default")
      (node (ref "1-25") (pin "2") (pinfunction "2_2") (pintype "passive"))
      (node (ref "ADDRESS_BUS") (pin "4") (pinfunction "4_4") (pintype "passive"))
      (node (ref "STM32F4") (pin "2") (pinfunction "PE3(5T)_2") (pintype "bidirectional"))
    )
    (net (code "84") (name "PE4") (class "Default")
      (node (ref "1-25") (pin "3") (pinfunction "3_3") (pintype "passive"))
      (node (ref "ADDRESS_BUS") (pin "5") (pinfunction "5_5") (pintype "passive"))
      (node (ref "STM32F4") (pin "3") (pinfunction "PE4(5T)_3") (pintype "bidirectional"))
    )
    (net (code "85") (name "PE5") (class "Default")
      (node (ref "1-25") (pin "4") (pinfunction "4_4") (pintype "passive"))
      (node (ref "ADDRESS_BUS") (pin "6") (pinfunction "6_6") (pintype "passive"))
      (node (ref "STM32F4") (pin "4") (pinfunction "PE5/TIM9_CH1(5T)_4") (pintype "bidirectional"))
    )
    (net (code "86") (name "PE6") (class "Default")
      (node (ref "1-25") (pin "5") (pinfunction "5_5") (pintype "passive"))
      (node (ref "ADDRESS_BUS") (pin "7") (pinfunction "7_7") (pintype "passive"))
      (node (ref "STM32F4") (pin "5") (pinfunction "PE6/TIM9_CH2(5T)_5") (pintype "bidirectional"))
    )
    (net (code "87") (name "PE7") (class "Default")
      (node (ref "26-50") (pin "13") (pinfunction "13_13") (pintype "passive"))
      (node (ref "ADDRESS_BUS") (pin "8") (pinfunction "8_8") (pintype "passive"))
      (node (ref "STM32F4") (pin "38") (pinfunction "PE7/TIM1_ETR(5T)_38") (pintype "bidirectional"))
    )
    (net (code "88") (name "PE8") (class "Default")
      (node (ref "26-50") (pin "14") (pinfunction "14_14") (pintype "passive"))
      (node (ref "ADDRESS_BUS") (pin "9") (pinfunction "9_9") (pintype "passive"))
      (node (ref "STM32F4") (pin "39") (pinfunction "PE8/TIM1_CH1N(5T)_39") (pintype "bidirectional"))
    )
    (net (code "89") (name "PE9") (class "Default")
      (node (ref "26-50") (pin "15") (pinfunction "15_15") (pintype "passive"))
      (node (ref "ADDRESS_BUS") (pin "10") (pinfunction "10_10") (pintype "passive"))
      (node (ref "STM32F4") (pin "40") (pinfunction "PE9/TIM1_CH1(5T)_40") (pintype "bidirectional"))
    )
    (net (code "90") (name "PE10") (class "Default")
      (node (ref "26-50") (pin "16") (pinfunction "16_16") (pintype "passive"))
      (node (ref "ADDRESS_BUS") (pin "11") (pinfunction "11_11") (pintype "passive"))
      (node (ref "STM32F4") (pin "41") (pinfunction "PE10/TIM1_CH2N(5T)_41") (pintype "bidirectional"))
    )
    (net (code "91") (name "PE11") (class "Default")
      (node (ref "26-50") (pin "17") (pinfunction "17_17") (pintype "passive"))
      (node (ref "ADDRESS_BUS") (pin "12") (pinfunction "12_12") (pintype "passive"))
      (node (ref "STM32F4") (pin "42") (pinfunction "PE11/TIM1_CH2(5T)_42") (pintype "bidirectional"))
    )
    (net (code "92") (name "PE12") (class "Default")
      (node (ref "26-50") (pin "18") (pinfunction "18_18") (pintype "passive"))
      (node (ref "ADDRESS_BUS") (pin "13") (pinfunction "13_13") (pintype "passive"))
      (node (ref "STM32F4") (pin "43") (pinfunction "PE12/TIM1_CH3N(5T)_43") (pintype "bidirectional"))
    )
    (net (code "93") (name "PE13") (class "Default")
      (node (ref "26-50") (pin "19") (pinfunction "19_19") (pintype "passive"))
      (node (ref "ADDRESS_BUS") (pin "14") (pinfunction "14_14") (pintype "passive"))
      (node (ref "STM32F4") (pin "44") (pinfunction "PE13/TIM1_CH3(5T)_44") (pintype "bidirectional"))
    )
    (net (code "94") (name "PE14") (class "Default")
      (node (ref "26-50") (pin "20") (pinfunction "20_20") (pintype "passive"))
      (node (ref "ADDRESS_BUS") (pin "15") (pinfunction "15_15") (pintype "passive"))
      (node (ref "STM32F4") (pin "45") (pinfunction "PE14/TIM1_CH4(5T)_45") (pintype "bidirectional"))
    )
    (net (code "95") (name "PE15") (class "Default")
      (node (ref "26-50") (pin "21") (pinfunction "21_21") (pintype "passive"))
      (node (ref "ADDRESS_BUS") (pin "16") (pinfunction "16_16") (pintype "passive"))
      (node (ref "STM32F4") (pin "46") (pinfunction "PE15/TIM1_BKIN(5T)_46") (pintype "bidirectional"))
    )
    (net (code "96") (name "PH0") (class "Default")
      (node (ref "1-25") (pin "12") (pinfunction "12_12") (pintype "passive"))
      (node (ref "C2") (pin "1") (pinfunction "1_1") (pintype "passive"))
      (node (ref "GPUOSC") (pin "2") (pinfunction "2_2") (pintype "passive"))
      (node (ref "STM32F4") (pin "12") (pinfunction "PH0-OSC_IN(5T)_12") (pintype "bidirectional"))
    )
    (net (code "97") (name "PH1") (class "Default")
      (node (ref "1-25") (pin "13") (pinfunction "13_13") (pintype "passive"))
      (node (ref "C5") (pin "1") (pinfunction "1_1") (pintype "passive"))
      (node (ref "GPUOSC") (pin "1") (pinfunction "1_1") (pintype "passive"))
      (node (ref "STM32F4") (pin "13") (pinfunction "PH1-OSC_OUT(5T)_13") (pintype "bidirectional"))
    )
    (net (code "98") (name "VBAT") (class "Default")
      (node (ref "1-25") (pin "6") (pinfunction "6_6") (pintype "passive"))
      (node (ref "STM32F4") (pin "6") (pinfunction "VBAT_6") (pintype "bidirectional"))
      (node (ref "VBATPWRJP") (pin "1") (pinfunction "1_1") (pintype "passive"))
    )
    (net (code "99") (name "VCAP_1") (class "Default")
      (node (ref "26-50") (pin "24") (pinfunction "24_24") (pintype "passive"))
      (node (ref "C9") (pin "1") (pinfunction "1_1") (pintype "passive"))
      (node (ref "STM32F4") (pin "49") (pinfunction "VCAP1_49") (pintype "bidirectional"))
    )
    (net (code "100") (name "VCAP_2") (class "Default")
      (node (ref "51-75") (pin "23") (pinfunction "23_23") (pintype "passive"))
      (node (ref "C8") (pin "1") (pinfunction "1_1") (pintype "passive"))
      (node (ref "STM32F4") (pin "73") (pinfunction "VCAP2_73") (pintype "bidirectional"))
    )
    (net (code "101") (name "VCC") (class "Default")
      (node (ref "PWRIN") (pin "1") (pinfunction "1_1") (pintype "passive"))
    )
    (net (code "102") (name "unconnected-(1-25-Pad26)") (class "Default")
      (node (ref "1-25") (pin "26") (pinfunction "26_26") (pintype "passive"))
    )
    (net (code "103") (name "unconnected-(26-50-Pad26)") (class "Default")
      (node (ref "26-50") (pin "26") (pinfunction "26_26") (pintype "passive"))
    )
    (net (code "104") (name "unconnected-(51-75-Pad26)") (class "Default")
      (node (ref "51-75") (pin "26") (pinfunction "26_26") (pintype "passive"))
    )
    (net (code "105") (name "unconnected-(76-100-Pad26)") (class "Default")
      (node (ref "76-100") (pin "26") (pinfunction "26_26") (pintype "passive"))
    )
    (net (code "106") (name "unconnected-(GPUHDR-Pad6)") (class "Default")
      (node (ref "GPUHDR") (pin "6") (pinfunction "6_6") (pintype "passive"))
    )
    (net (code "107") (name "unconnected-(IOHDR-Pad3)") (class "Default")
      (node (ref "IOHDR") (pin "3") (pinfunction "3_3") (pintype "passive"))
    )
    (net (code "108") (name "unconnected-(IOHDR-Pad4)") (class "Default")
      (node (ref "IOHDR") (pin "4") (pinfunction "4_4") (pintype "passive"))
    )
    (net (code "109") (name "unconnected-(IOHDR-Pad5)") (class "Default")
      (node (ref "IOHDR") (pin "5") (pinfunction "5_5") (pintype "passive"))
    )
    (net (code "110") (name "unconnected-(ISPJTAG-Pad4)") (class "Default")
      (node (ref "ISPJTAG") (pin "4") (pinfunction "4_4") (pintype "passive"))
    )
    (net (code "111") (name "unconnected-(ISPJTAG-Pad6)") (class "Default")
      (node (ref "ISPJTAG") (pin "6") (pinfunction "6_6") (pintype "passive"))
    )
    (net (code "112") (name "unconnected-(ISPJTAG-Pad8)") (class "Default")
      (node (ref "ISPJTAG") (pin "8") (pinfunction "8_8") (pintype "passive"))
    )
    (net (code "113") (name "unconnected-(ISPJTAG-Pad10)") (class "Default")
      (node (ref "ISPJTAG") (pin "10") (pinfunction "10_10") (pintype "passive"))
    )
    (net (code "114") (name "unconnected-(ISPJTAG-Pad11)") (class "Default")
      (node (ref "ISPJTAG") (pin "11") (pinfunction "11_11") (pintype "passive"))
    )
    (net (code "115") (name "unconnected-(ISPJTAG-Pad16)") (class "Default")
      (node (ref "ISPJTAG") (pin "16") (pinfunction "16_16") (pintype "passive"))
    )
    (net (code "116") (name "unconnected-(ISPJTAG-Pad17)") (class "Default")
      (node (ref "ISPJTAG") (pin "17") (pinfunction "17_17") (pintype "passive"))
    )
    (net (code "117") (name "unconnected-(ISPJTAG-Pad19)") (class "Default")
      (node (ref "ISPJTAG") (pin "19") (pinfunction "19_19") (pintype "passive"))
    )
  )
)
